# ADJ_Power_managment.net
KiCad netlist of a schematic drawn in Altium Designer
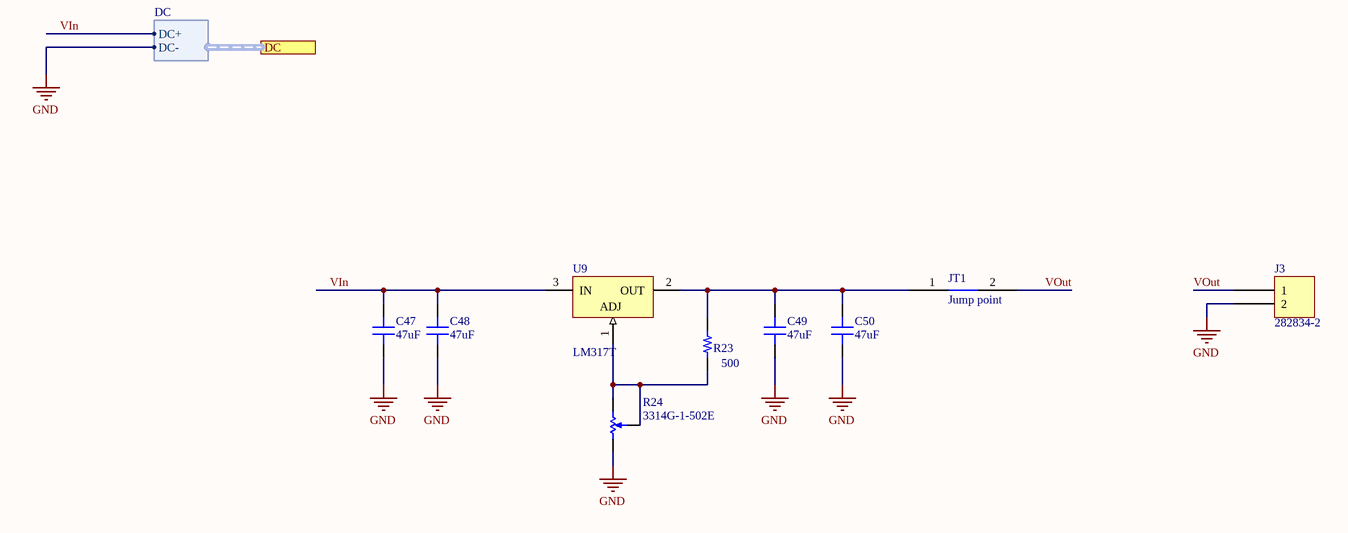
[diagram p0: ADJ Power managment.SchDoc]

(export (version "E")
  (design (tool "Eeschema 10.0.6"))
  (components
    (comp (ref "C47")
      (value "47uF")
      (footprint "CAP 0805_2012")
      (description "CAP CER 33PF 250V C0G/NP0 0805")
      (fields (field (name "PART NUMBER") "CBR08C330JAGAC") (field (name "MANUFACTURER") "KEMET"))
      (libsource (lib "Celestial Altium Library - altium_library (2)") (part "Capacitor"))
    )
    (comp (ref "C48")
      (value "47uF")
      (footprint "CAP 0805_2012")
      (description "CAP CER 33PF 250V C0G/NP0 0805")
      (fields (field (name "PART NUMBER") "CBR08C330JAGAC") (field (name "MANUFACTURER") "KEMET"))
      (libsource (lib "Celestial Altium Library - altium_library (2)") (part "Capacitor"))
    )
    (comp (ref "C49")
      (value "47uF")
      (footprint "CAP 0805_2012")
      (description "CAP CER 33PF 250V C0G/NP0 0805")
      (fields (field (name "PART NUMBER") "CBR08C330JAGAC") (field (name "MANUFACTURER") "KEMET"))
      (libsource (lib "Celestial Altium Library - altium_library (2)") (part "Capacitor"))
    )
    (comp (ref "C50")
      (value "47uF")
      (footprint "CAP 0805_2012")
      (description "CAP CER 33PF 250V C0G/NP0 0805")
      (fields (field (name "PART NUMBER") "CBR08C330JAGAC") (field (name "MANUFACTURER") "KEMET"))
      (libsource (lib "Celestial Altium Library - altium_library (2)") (part "Capacitor"))
    )
    (comp (ref "J3")
      (value "282834-2")
      (footprint "TE 282834-2")
      (description "TERM BLK 2P SIDE ENT 2.54MM PCB")
      (fields (field (name "MANUFACTURER") "TE Connectivity AMP Connectors") (field (name "VOLTAGE") "150V"))
      (libsource (lib "Celestial Altium Library - altium_library (2)") (part "2 Pin"))
    )
    (comp (ref "JT1")
      (value "Jump point")
      (footprint "jump poınt")
      (libsource (lib "Schlib1") (part "Jump point"))
    )
    (comp (ref "R23")
      (value "500")
      (footprint "RES 0805_2012")
      (description "RES 500 OHM JUMPER 0805")
      (fields
        (field (name "PART NUMBER") "TLRZ2ATTD")
        (field (name "MANUFACTURER") "KOA Speer Electronics, Inc.")
      )
      (libsource (lib "Celestial Altium Library - altium_library (2)") (part "Resistor"))
    )
    (comp (ref "R24")
      (value "3314G-1-502E")
      (footprint "BOUR-3314G-1_V")
      (fields
        (field (name "POWER") "250")
        (field (name "TOLERANCE") "±20%")
        (field (name "MANUFACTURER") "Bourns")
      )
      (libsource (lib "Altium Content Vault") (part "RES-ADJ-3_A"))
    )
    (comp (ref "U9")
      (value "LM317T")
      (footprint "NDE0003A")
      (description "3-Terminal Adjustable Regulator, 3-pin TO-220")
      (fields (field (name "MANUFACTURER") "Texas Instruments"))
      (libsource (lib "Altium Content Vault") (part "PM-REG-LM1086ADJ-SIL3"))
    )
  )
  (nets
    (net (code "2") (name "/VIn") (class "Default")
      (node (ref "C47") (pin "2") (pinfunction "2_2") (pintype "passive"))
      (node (ref "C48") (pin "2") (pinfunction "2_2") (pintype "passive"))
      (node (ref "U9") (pin "3") (pinfunction "IN_3") (pintype "power_in"))
    )
    (net (code "3") (name "/VOut") (class "Default")
      (node (ref "J3") (pin "1") (pinfunction "1_1") (pintype "passive"))
      (node (ref "JT1") (pin "2") (pinfunction "2_2") (pintype "passive"))
    )
    (net (code "5") (name "GND") (class "Default")
      (node (ref "C47") (pin "1") (pinfunction "1_1") (pintype "passive"))
      (node (ref "C48") (pin "1") (pinfunction "1_1") (pintype "passive"))
      (node (ref "C49") (pin "1") (pinfunction "1_1") (pintype "passive"))
      (node (ref "C50") (pin "1") (pinfunction "1_1") (pintype "passive"))
      (node (ref "J3") (pin "2") (pinfunction "2_2") (pintype "passive"))
      (node (ref "R24") (pin "1") (pinfunction "1_1") (pintype "passive"))
    )
    (net (code "6") (name "Net-(JT1-0)") (class "Default")
      (node (ref "C49") (pin "2") (pinfunction "2_2") (pintype "passive"))
      (node (ref "C50") (pin "2") (pinfunction "2_2") (pintype "passive"))
      (node (ref "JT1") (pin "1") (pinfunction "0_1") (pintype "passive"))
      (node (ref "R23") (pin "2") (pinfunction "2_2") (pintype "passive"))
      (node (ref "U9") (pin "2") (pinfunction "OUT_2") (pintype "power_in"))
    )
    (net (code "7") (name "Net-(U9-ADJ)") (class "Default")
      (node (ref "R23") (pin "1") (pinfunction "1_1") (pintype "passive"))
      (node (ref "R24") (pin "2") (pinfunction "2_2") (pintype "passive"))
      (node (ref "R24") (pin "3") (pinfunction "3_3") (pintype "passive"))
      (node (ref "U9") (pin "1") (pinfunction "ADJ_1") (pintype "input"))
    )
  )
)
